# water-pump.net
KiCad netlist of a schematic drawn in EAGLE
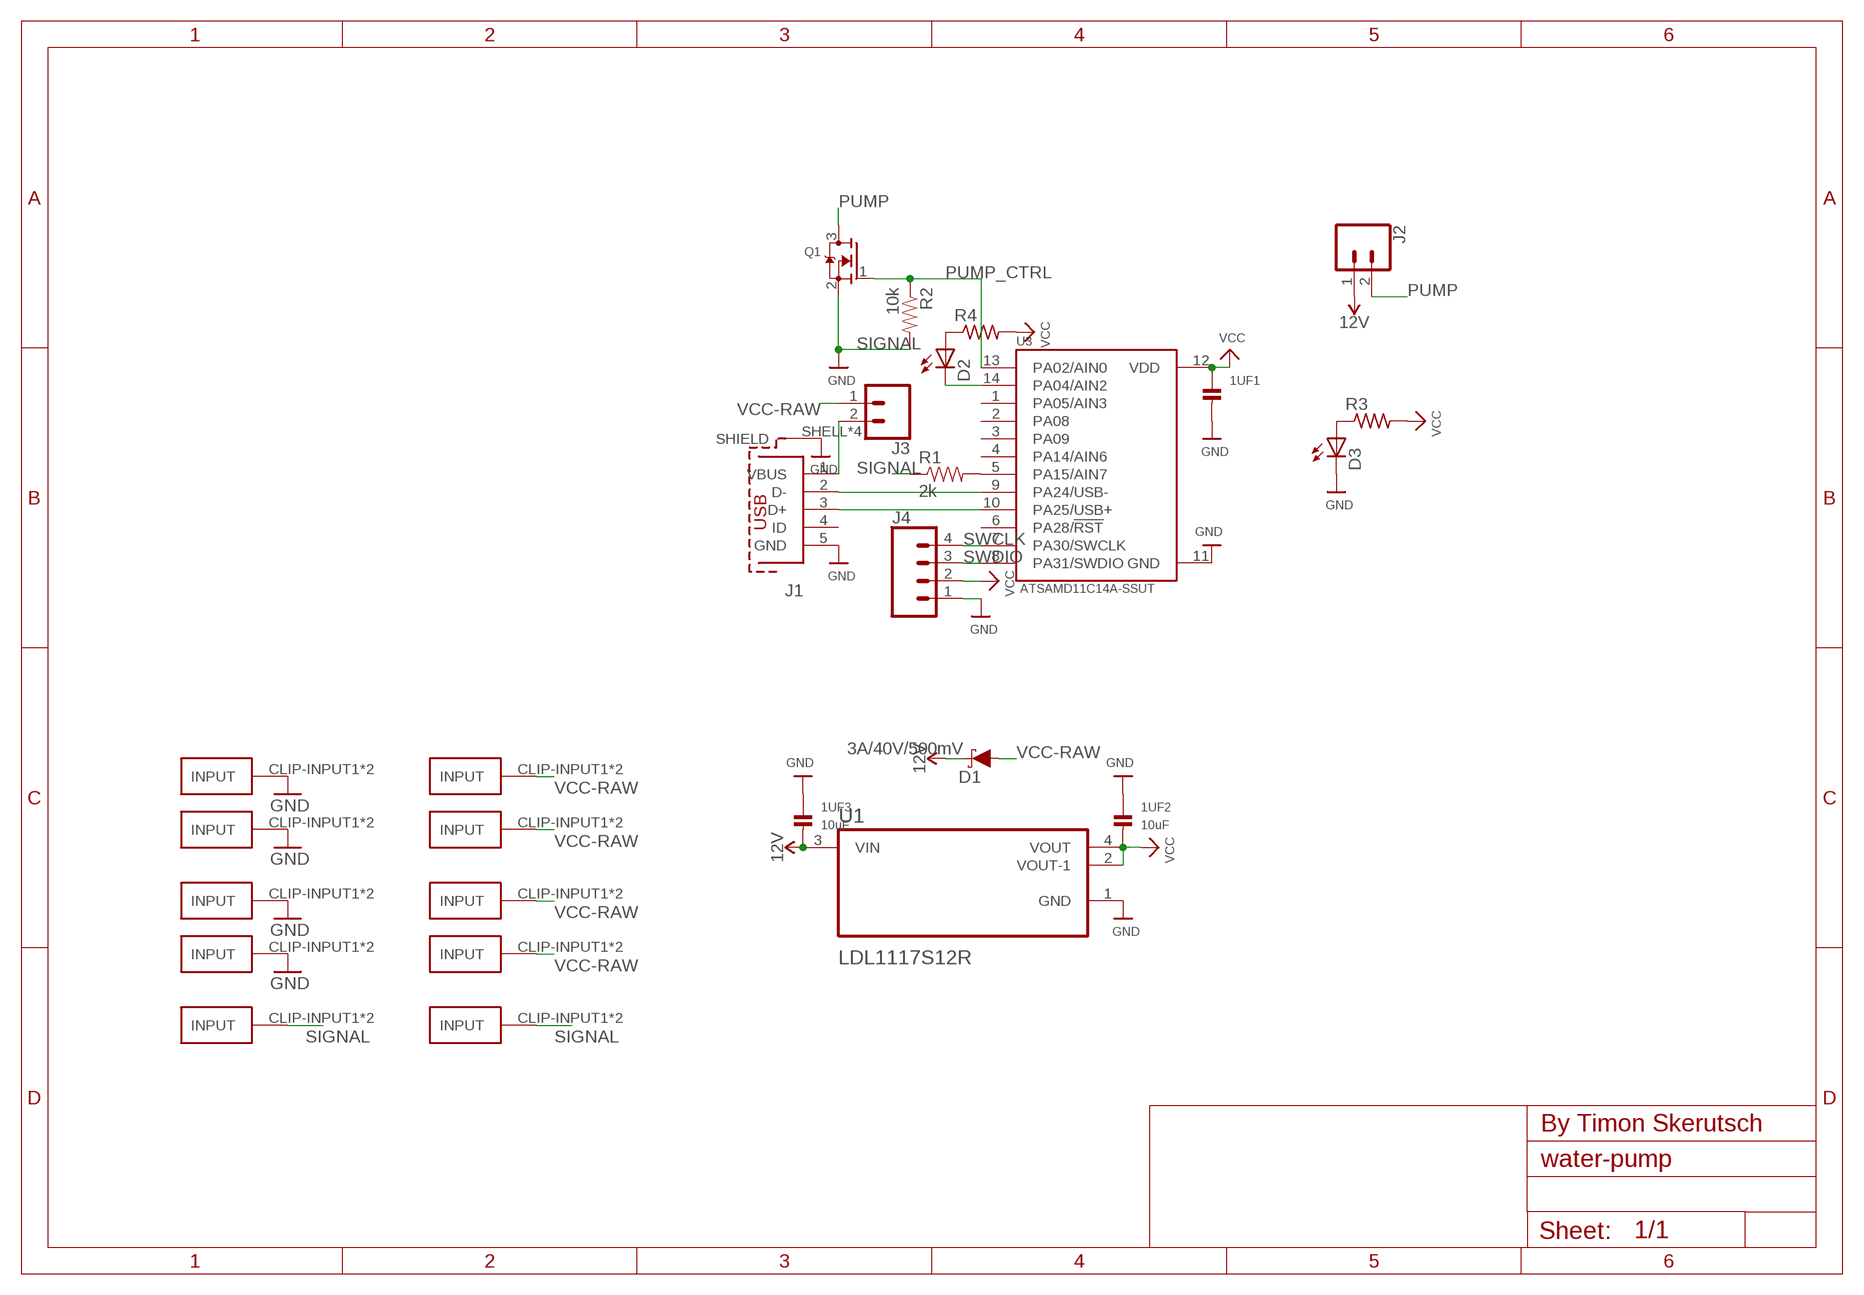
[diagram p0: schematic, sheet 1]

(export (version "E")
  (design (tool "Eeschema 10.0.6"))
  (components
    (comp (ref "1UF1")
      (value "CAP_CERAMIC0603")
      (footprint "eagle-import:0603")
      (libsource (lib "eagle-import") (part "CAP_CERAMIC0603"))
    )
    (comp (ref "1UF2")
      (value "10uF")
      (footprint "eagle-import:0805")
      (libsource (lib "eagle-import") (part "CAP_CERAMIC0805"))
    )
    (comp (ref "1UF3")
      (value "10uF")
      (footprint "eagle-import:0805")
      (libsource (lib "eagle-import") (part "CAP_CERAMIC0805"))
    )
    (comp (ref "D1")
      (value "3A/40V/500mV")
      (footprint "eagle-import:SMA-DIODE")
      (libsource (lib "eagle-import") (part "DIODE-SCHOTTKY-B340A"))
    )
    (comp (ref "D2")
      (value "LEDCHIPLED_0805")
      (footprint "eagle-import:CHIPLED_0805")
      (libsource (lib "eagle-import") (part "LEDCHIPLED_0805"))
    )
    (comp (ref "D3")
      (value "LEDCHIPLED_0805")
      (footprint "eagle-import:CHIPLED_0805")
      (libsource (lib "eagle-import") (part "LEDCHIPLED_0805"))
    )
    (comp (ref "GND-CLIP")
      (value "FUSE-HOLDER-5X20MM")
      (footprint "eagle-import:FUSE-HOLDER-5X20MM")
      (libsource (lib "eagle-import") (part "FUSE-HOLDER-5X20MM"))
    )
    (comp (ref "GND-CLIP1")
      (value "FUSE-HOLDER-5X20MM")
      (footprint "eagle-import:FUSE-HOLDER-5X20MM")
      (libsource (lib "eagle-import") (part "FUSE-HOLDER-5X20MM"))
    )
    (comp (ref "GND-CLIP2")
      (value "FUSE-HOLDER-5X20MM")
      (footprint "eagle-import:FUSE-HOLDER-5X20MM")
      (libsource (lib "eagle-import") (part "FUSE-HOLDER-5X20MM"))
    )
    (comp (ref "GND-CLIP3")
      (value "FUSE-HOLDER-5X20MM")
      (footprint "eagle-import:FUSE-HOLDER-5X20MM")
      (libsource (lib "eagle-import") (part "FUSE-HOLDER-5X20MM"))
    )
    (comp (ref "J1")
      (value "629105136821")
      (footprint "eagle-import:629105136821")
      (libsource (lib "eagle-import") (part "629105136821"))
    )
    (comp (ref "J2")
      (value "CONN_02PTH3")
      (footprint "eagle-import:1X02_LONGPADS")
      (libsource (lib "eagle-import") (part "CONN_02PTH3"))
    )
    (comp (ref "J3")
      (value "CONN_02PTH3")
      (footprint "eagle-import:1X02_LONGPADS")
      (libsource (lib "eagle-import") (part "CONN_02PTH3"))
    )
    (comp (ref "J4")
      (value "CONN_04")
      (footprint "eagle-import:1X04")
      (libsource (lib "eagle-import") (part "CONN_04"))
    )
    (comp (ref "PWM-CLIP")
      (value "FUSE-HOLDER-5X20MM")
      (footprint "eagle-import:FUSE-HOLDER-5X20MM")
      (libsource (lib "eagle-import") (part "FUSE-HOLDER-5X20MM"))
    )
    (comp (ref "PWM-CLIP1")
      (value "FUSE-HOLDER-5X20MM")
      (footprint "eagle-import:FUSE-HOLDER-5X20MM")
      (libsource (lib "eagle-import") (part "FUSE-HOLDER-5X20MM"))
    )
    (comp (ref "Q1")
      (value "MOSFET-NWIDE")
      (footprint "eagle-import:SOT23-WIDE")
      (libsource (lib "eagle-import") (part "MOSFET-NWIDE"))
    )
    (comp (ref "R1")
      (value "2k")
      (footprint "eagle-import:1206")
      (libsource (lib "eagle-import") (part "RESISTOR1206"))
    )
    (comp (ref "R2")
      (value "10k")
      (footprint "eagle-import:1206")
      (libsource (lib "eagle-import") (part "RESISTOR1206"))
    )
    (comp (ref "R3")
      (value "R-US_R0805")
      (footprint "eagle-import:R0805")
      (libsource (lib "eagle-import") (part "R-US_R0805"))
    )
    (comp (ref "R4")
      (value "R-US_R0805")
      (footprint "eagle-import:R0805")
      (libsource (lib "eagle-import") (part "R-US_R0805"))
    )
    (comp (ref "U1")
      (value "LDL1117S12R")
      (footprint "eagle-import:SOT230P700X180-4N")
      (fields (field (name "MF") "STMicroelectronics"))
      (libsource (lib "eagle-import") (part "LDL1117S12R"))
    )
    (comp (ref "U3")
      (value "ATSAMD11C14A-SSUT")
      (footprint "eagle-import:SOIC127P600X160-14N")
      (fields (field (name "MF") "Microchip"))
      (libsource (lib "eagle-import") (part "ATSAMD11C14A-SSUT"))
    )
    (comp (ref "VCC-CLIP")
      (value "FUSE-HOLDER-5X20MM")
      (footprint "eagle-import:FUSE-HOLDER-5X20MM")
      (libsource (lib "eagle-import") (part "FUSE-HOLDER-5X20MM"))
    )
    (comp (ref "VCC-CLIP1")
      (value "FUSE-HOLDER-5X20MM")
      (footprint "eagle-import:FUSE-HOLDER-5X20MM")
      (libsource (lib "eagle-import") (part "FUSE-HOLDER-5X20MM"))
    )
    (comp (ref "VCC-CLIP2")
      (value "FUSE-HOLDER-5X20MM")
      (footprint "eagle-import:FUSE-HOLDER-5X20MM")
      (libsource (lib "eagle-import") (part "FUSE-HOLDER-5X20MM"))
    )
    (comp (ref "VCC-CLIP3")
      (value "FUSE-HOLDER-5X20MM")
      (footprint "eagle-import:FUSE-HOLDER-5X20MM")
      (libsource (lib "eagle-import") (part "FUSE-HOLDER-5X20MM"))
    )
  )
  (nets
    (net (code "1") (name "/PUMP") (class "Default")
      (node (ref "J2") (pin "2") (pinfunction "2_2") (pintype "passive"))
      (node (ref "Q1") (pin "3") (pinfunction "D_3") (pintype "bidirectional"))
    )
    (net (code "2") (name "/PUMP_CTRL") (class "Default")
      (node (ref "Q1") (pin "1") (pinfunction "G_1") (pintype "bidirectional"))
      (node (ref "R2") (pin "1") (pinfunction "1_1") (pintype "passive"))
      (node (ref "U3") (pin "13") (pinfunction "PA02/AIN0_13") (pintype "bidirectional"))
    )
    (net (code "3") (name "/SIGNAL") (class "Default")
      (node (ref "PWM-CLIP") (pin "CLIP-INPUT1") (pinfunction "INPUT_CLIP-INPUT1") (pintype "bidirectional"))
      (node (ref "PWM-CLIP") (pin "CLIP-INPUT2") (pinfunction "INPUT_CLIP-INPUT2") (pintype "bidirectional"))
      (node (ref "PWM-CLIP1") (pin "CLIP-INPUT1") (pinfunction "INPUT_CLIP-INPUT1") (pintype "bidirectional"))
      (node (ref "PWM-CLIP1") (pin "CLIP-INPUT2") (pinfunction "INPUT_CLIP-INPUT2") (pintype "bidirectional"))
      (node (ref "R1") (pin "1") (pinfunction "1_1") (pintype "passive"))
    )
    (net (code "4") (name "/SWCLK") (class "Default")
      (node (ref "J4") (pin "4") (pinfunction "4_4") (pintype "passive"))
      (node (ref "U3") (pin "7") (pinfunction "PA30/SWCLK_7") (pintype "bidirectional"))
    )
    (net (code "5") (name "/SWDIO") (class "Default")
      (node (ref "J4") (pin "3") (pinfunction "3_3") (pintype "passive"))
      (node (ref "U3") (pin "8") (pinfunction "PA31/SWDIO_8") (pintype "bidirectional"))
    )
    (net (code "6") (name "/VCC-RAW") (class "Default")
      (node (ref "D1") (pin "A") (pinfunction "A_A") (pintype "passive"))
      (node (ref "J3") (pin "1") (pinfunction "1_1") (pintype "passive"))
      (node (ref "VCC-CLIP") (pin "CLIP-INPUT1") (pinfunction "INPUT_CLIP-INPUT1") (pintype "bidirectional"))
      (node (ref "VCC-CLIP") (pin "CLIP-INPUT2") (pinfunction "INPUT_CLIP-INPUT2") (pintype "bidirectional"))
      (node (ref "VCC-CLIP1") (pin "CLIP-INPUT1") (pinfunction "INPUT_CLIP-INPUT1") (pintype "bidirectional"))
      (node (ref "VCC-CLIP1") (pin "CLIP-INPUT2") (pinfunction "INPUT_CLIP-INPUT2") (pintype "bidirectional"))
      (node (ref "VCC-CLIP2") (pin "CLIP-INPUT1") (pinfunction "INPUT_CLIP-INPUT1") (pintype "bidirectional"))
      (node (ref "VCC-CLIP2") (pin "CLIP-INPUT2") (pinfunction "INPUT_CLIP-INPUT2") (pintype "bidirectional"))
      (node (ref "VCC-CLIP3") (pin "CLIP-INPUT1") (pinfunction "INPUT_CLIP-INPUT1") (pintype "bidirectional"))
      (node (ref "VCC-CLIP3") (pin "CLIP-INPUT2") (pinfunction "INPUT_CLIP-INPUT2") (pintype "bidirectional"))
    )
    (net (code "7") (name "12V") (class "Default")
      (node (ref "1UF3") (pin "2") (pinfunction "P$2_2") (pintype "passive"))
      (node (ref "D1") (pin "C") (pinfunction "C_C") (pintype "passive"))
      (node (ref "J2") (pin "1") (pinfunction "1_1") (pintype "passive"))
      (node (ref "U1") (pin "3") (pinfunction "VIN_3") (pintype "input"))
    )
    (net (code "8") (name "GND") (class "Default")
      (node (ref "1UF1") (pin "2") (pinfunction "P$2_2") (pintype "passive"))
      (node (ref "1UF2") (pin "1") (pinfunction "P$1_1") (pintype "passive"))
      (node (ref "1UF3") (pin "1") (pinfunction "P$1_1") (pintype "passive"))
      (node (ref "D3") (pin "C") (pinfunction "C_C") (pintype "passive"))
      (node (ref "GND-CLIP") (pin "CLIP-INPUT1") (pinfunction "INPUT_CLIP-INPUT1") (pintype "bidirectional"))
      (node (ref "GND-CLIP") (pin "CLIP-INPUT2") (pinfunction "INPUT_CLIP-INPUT2") (pintype "bidirectional"))
      (node (ref "GND-CLIP1") (pin "CLIP-INPUT1") (pinfunction "INPUT_CLIP-INPUT1") (pintype "bidirectional"))
      (node (ref "GND-CLIP1") (pin "CLIP-INPUT2") (pinfunction "INPUT_CLIP-INPUT2") (pintype "bidirectional"))
      (node (ref "GND-CLIP2") (pin "CLIP-INPUT1") (pinfunction "INPUT_CLIP-INPUT1") (pintype "bidirectional"))
      (node (ref "GND-CLIP2") (pin "CLIP-INPUT2") (pinfunction "INPUT_CLIP-INPUT2") (pintype "bidirectional"))
      (node (ref "GND-CLIP3") (pin "CLIP-INPUT1") (pinfunction "INPUT_CLIP-INPUT1") (pintype "bidirectional"))
      (node (ref "GND-CLIP3") (pin "CLIP-INPUT2") (pinfunction "INPUT_CLIP-INPUT2") (pintype "bidirectional"))
      (node (ref "J1") (pin "5") (pinfunction "GND_5") (pintype "passive"))
      (node (ref "J1") (pin "SHELL") (pinfunction "SHIELD_SHELL") (pintype "passive"))
      (node (ref "J1") (pin "SHELL1") (pinfunction "SHIELD_SHELL1") (pintype "passive"))
      (node (ref "J1") (pin "SHELL2") (pinfunction "SHIELD_SHELL2") (pintype "passive"))
      (node (ref "J1") (pin "SHELL3") (pinfunction "SHIELD_SHELL3") (pintype "passive"))
      (node (ref "J4") (pin "1") (pinfunction "1_1") (pintype "passive"))
      (node (ref "Q1") (pin "2") (pinfunction "S_2") (pintype "bidirectional"))
      (node (ref "R2") (pin "2") (pinfunction "2_2") (pintype "passive"))
      (node (ref "U1") (pin "1") (pinfunction "GND_1") (pintype "power_in"))
      (node (ref "U3") (pin "11") (pinfunction "GND_11") (pintype "power_in"))
    )
    (net (code "9") (name "Net-(D2-PadA)") (class "Default")
      (node (ref "D2") (pin "A") (pinfunction "A_A") (pintype "passive"))
      (node (ref "R4") (pin "1") (pinfunction "1_1") (pintype "passive"))
    )
    (net (code "10") (name "Net-(D3-PadA)") (class "Default")
      (node (ref "D3") (pin "A") (pinfunction "A_A") (pintype "passive"))
      (node (ref "R3") (pin "1") (pinfunction "1_1") (pintype "passive"))
    )
    (net (code "11") (name "Net-(J1-D+)") (class "Default")
      (node (ref "J1") (pin "3") (pinfunction "D+_3") (pintype "passive"))
      (node (ref "U3") (pin "10") (pinfunction "PA25/USB+_10") (pintype "bidirectional"))
    )
    (net (code "12") (name "Net-(J1-D-)") (class "Default")
      (node (ref "J1") (pin "2") (pinfunction "D-_2") (pintype "passive"))
      (node (ref "U3") (pin "9") (pinfunction "PA24/USB-_9") (pintype "bidirectional"))
    )
    (net (code "13") (name "Net-(J1-VBUS)") (class "Default")
      (node (ref "J1") (pin "1") (pinfunction "VBUS_1") (pintype "passive"))
      (node (ref "J3") (pin "2") (pinfunction "2_2") (pintype "passive"))
    )
    (net (code "14") (name "Net-(U3-PA04{slash}AIN2)") (class "Default")
      (node (ref "D2") (pin "C") (pinfunction "C_C") (pintype "passive"))
      (node (ref "U3") (pin "14") (pinfunction "PA04/AIN2_14") (pintype "bidirectional"))
    )
    (net (code "15") (name "Net-(U3-PA15{slash}AIN7)") (class "Default")
      (node (ref "R1") (pin "2") (pinfunction "2_2") (pintype "passive"))
      (node (ref "U3") (pin "5") (pinfunction "PA15/AIN7_5") (pintype "bidirectional"))
    )
    (net (code "16") (name "VCC") (class "Default")
      (node (ref "1UF1") (pin "1") (pinfunction "P$1_1") (pintype "passive"))
      (node (ref "1UF2") (pin "2") (pinfunction "P$2_2") (pintype "passive"))
      (node (ref "J4") (pin "2") (pinfunction "2_2") (pintype "passive"))
      (node (ref "R3") (pin "2") (pinfunction "2_2") (pintype "passive"))
      (node (ref "R4") (pin "2") (pinfunction "2_2") (pintype "passive"))
      (node (ref "U1") (pin "2") (pinfunction "VOUT-1_2") (pintype "output"))
      (node (ref "U1") (pin "4") (pinfunction "VOUT_4") (pintype "output"))
      (node (ref "U3") (pin "12") (pinfunction "VDD_12") (pintype "power_in"))
    )
    (net (code "17") (name "unconnected-(J1-ID-Pad4)") (class "Default")
      (node (ref "J1") (pin "4") (pinfunction "ID_4") (pintype "passive"))
    )
    (net (code "18") (name "unconnected-(U3-PA05{slash}AIN3-Pad1)") (class "Default")
      (node (ref "U3") (pin "1") (pinfunction "PA05/AIN3_1") (pintype "bidirectional"))
    )
    (net (code "19") (name "unconnected-(U3-PA08-Pad2)") (class "Default")
      (node (ref "U3") (pin "2") (pinfunction "PA08_2") (pintype "bidirectional"))
    )
    (net (code "20") (name "unconnected-(U3-PA09-Pad3)") (class "Default")
      (node (ref "U3") (pin "3") (pinfunction "PA09_3") (pintype "bidirectional"))
    )
    (net (code "21") (name "unconnected-(U3-PA14{slash}AIN6-Pad4)") (class "Default")
      (node (ref "U3") (pin "4") (pinfunction "PA14/AIN6_4") (pintype "bidirectional"))
    )
    (net (code "22") (name "unconnected-(U3-PA28{slash}~{RST}-Pad6)") (class "Default")
      (node (ref "U3") (pin "6") (pinfunction "PA28/~{RST}_6") (pintype "bidirectional"))
    )
  )
)
